# LIN_break.net
KiCad netlist of a schematic drawn in Altium Designer
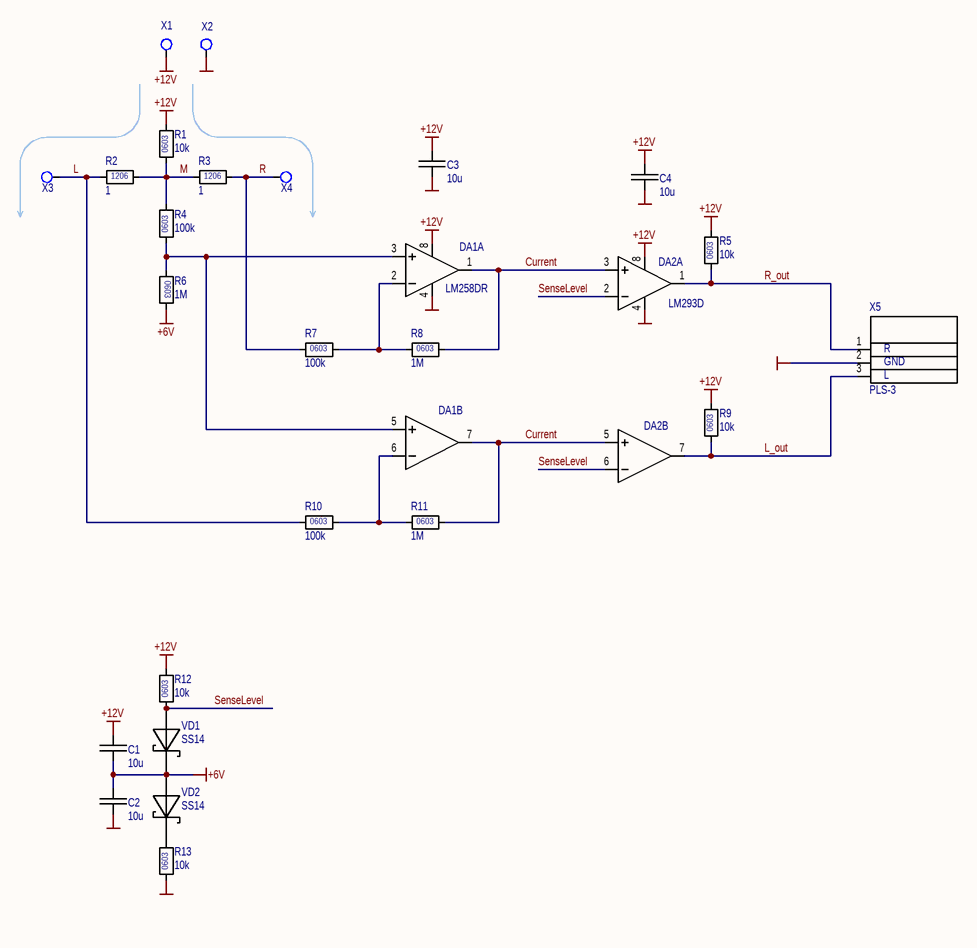
[diagram p0: LIN_break.SchDoc]

(export (version "E")
  (design (tool "Eeschema 10.0.6"))
  (components
    (comp (ref "C1")
      (value "10u")
      (footprint "C0603")
      (description "General  ceramic capacitor")
      (fields
        (field (name "PART NUMBER") "GRM188R61E106MA73#")
        (field (name "ALT PART") "C1608X5R106MFT(Darfon) C1608X5R1E106M080AC(TDK)")
      )
      (libsource (lib "altium") (part "Capacitor"))
    )
    (comp (ref "C2")
      (value "10u")
      (footprint "C0603")
      (description "General  ceramic capacitor")
      (fields
        (field (name "PART NUMBER") "GRM188R61E106MA73#")
        (field (name "ALT PART") "C1608X5R106MFT(Darfon) C1608X5R1E106M080AC(TDK)")
      )
      (libsource (lib "altium") (part "Capacitor"))
    )
    (comp (ref "C3")
      (value "10u")
      (footprint "C0603")
      (description "General  ceramic capacitor")
      (fields
        (field (name "PART NUMBER") "GRM188R61E106MA73#")
        (field (name "ALT PART") "C1608X5R106MFT(Darfon) C1608X5R1E106M080AC(TDK)")
      )
      (libsource (lib "altium") (part "Capacitor"))
    )
    (comp (ref "C4")
      (value "10u")
      (footprint "C0603")
      (description "General  ceramic capacitor")
      (fields
        (field (name "PART NUMBER") "GRM188R61E106MA73#")
        (field (name "ALT PART") "C1608X5R106MFT(Darfon) C1608X5R1E106M080AC(TDK)")
      )
      (libsource (lib "altium") (part "Capacitor"))
    )
    (comp (ref "DA1")
      (value "LM258")
      (footprint "TI-SOIC8 D")
      (description "Op Amp")
      (fields (field (name "PART NUMBER") "LM258DR"))
      (libsource (lib "altium") (part "LMx58_LM2904"))
    )
    (comp (ref "DA2")
      (value "Comparator")
      (footprint "TI-SOIC8 D")
      (description "Dual Comparator OK")
      (fields (field (name "PART NUMBER") "LM293D"))
      (libsource (lib "altium") (part "LMx93_LM2903"))
    )
    (comp (ref "R1")
      (value "10k")
      (footprint "R0603")
      (description "Thick Film Chip Resistor - CR Series")
      (fields (field (name "PART NUMBER") "CR-03FL7---10k") (field (name "ALT PART") "RTT031002FTH (Ralec)"))
      (libsource (lib "altium") (part "Resistor - 0603"))
    )
    (comp (ref "R2")
      (value "1")
      (footprint "R1206")
      (description "1/4W 200V")
      (fields (field (name "PART NUMBER") "CR-06FL5---1R0") (field (name "POWER") "1/4W"))
      (libsource (lib "altium") (part "Resistor - 1206"))
    )
    (comp (ref "R3")
      (value "1")
      (footprint "R1206")
      (description "1/4W 200V")
      (fields (field (name "PART NUMBER") "CR-06FL5---1R0") (field (name "POWER") "1/4W"))
      (libsource (lib "altium") (part "Resistor - 1206"))
    )
    (comp (ref "R4")
      (value "100k")
      (footprint "R0603")
      (description "Thick Film Chip Resistor - CR Series")
      (fields (field (name "PART NUMBER") "CR-03FL7----1M") (field (name "ALT PART") "RTT031004FTH (Ralec)"))
      (libsource (lib "altium") (part "Resistor - 0603"))
    )
    (comp (ref "R5")
      (value "10k")
      (footprint "R0603")
      (description "Thick Film Chip Resistor - CR Series")
      (fields (field (name "PART NUMBER") "CR-03FL7---10k") (field (name "ALT PART") "RTT031002FTH (Ralec)"))
      (libsource (lib "altium") (part "Resistor - 0603"))
    )
    (comp (ref "R6")
      (value "1M")
      (footprint "R0603")
      (description "Thick Film Chip Resistor - CR Series")
      (fields (field (name "PART NUMBER") "CR-03FL7----1M") (field (name "ALT PART") "RTT031004FTH (Ralec)"))
      (libsource (lib "altium") (part "Resistor - 0603"))
    )
    (comp (ref "R7")
      (value "100k")
      (footprint "R0603")
      (description "Thick Film Chip Resistor - CR Series")
      (fields (field (name "PART NUMBER") "CR-03FL7----1M") (field (name "ALT PART") "RTT031004FTH (Ralec)"))
      (libsource (lib "altium") (part "Resistor - 0603"))
    )
    (comp (ref "R8")
      (value "1M")
      (footprint "R0603")
      (description "Thick Film Chip Resistor - CR Series")
      (fields (field (name "PART NUMBER") "CR-03FL7----1M") (field (name "ALT PART") "RTT031004FTH (Ralec)"))
      (libsource (lib "altium") (part "Resistor - 0603"))
    )
    (comp (ref "R9")
      (value "10k")
      (footprint "R0603")
      (description "Thick Film Chip Resistor - CR Series")
      (fields (field (name "PART NUMBER") "CR-03FL7---10k") (field (name "ALT PART") "RTT031002FTH (Ralec)"))
      (libsource (lib "altium") (part "Resistor - 0603"))
    )
    (comp (ref "R10")
      (value "100k")
      (footprint "R0603")
      (description "Thick Film Chip Resistor - CR Series")
      (fields (field (name "PART NUMBER") "CR-03FL7----1M") (field (name "ALT PART") "RTT031004FTH (Ralec)"))
      (libsource (lib "altium") (part "Resistor - 0603"))
    )
    (comp (ref "R11")
      (value "1M")
      (footprint "R0603")
      (description "Thick Film Chip Resistor - CR Series")
      (fields (field (name "PART NUMBER") "CR-03FL7----1M") (field (name "ALT PART") "RTT031004FTH (Ralec)"))
      (libsource (lib "altium") (part "Resistor - 0603"))
    )
    (comp (ref "R12")
      (value "10k")
      (footprint "R0603")
      (description "Thick Film Chip Resistor - CR Series")
      (fields (field (name "PART NUMBER") "CR-03FL7---10k") (field (name "ALT PART") "RTT031002FTH (Ralec)"))
      (libsource (lib "altium") (part "Resistor - 0603"))
    )
    (comp (ref "R13")
      (value "10k")
      (footprint "R0603")
      (description "Thick Film Chip Resistor - CR Series")
      (fields (field (name "PART NUMBER") "CR-03FL7---10k") (field (name "ALT PART") "RTT031002FTH (Ralec)"))
      (libsource (lib "altium") (part "Resistor - 0603"))
    )
    (comp (ref "VD1")
      (value "SS14")
      (footprint "DO-214AC(SMA)")
      (description "40V 1A Schottky diode")
      (libsource (lib "altium") (part "Schottky diode"))
    )
    (comp (ref "VD2")
      (value "SS14")
      (footprint "DO-214AC(SMA)")
      (description "40V 1A Schottky diode")
      (libsource (lib "altium") (part "Schottky diode"))
    )
    (comp (ref "X1")
      (value "1-pin_round NB")
      (footprint "Hole-2.4-5")
      (description "M2 x .4 Screw with Lock Washer")
      (libsource (lib "altium") (part "1-pin_round NB"))
    )
    (comp (ref "X2")
      (value "1-pin_round NB")
      (footprint "Hole-2.4-5")
      (description "M2 x .4 Screw with Lock Washer")
      (libsource (lib "altium") (part "1-pin_round NB"))
    )
    (comp (ref "X3")
      (value "1-pin_round NB")
      (footprint "Hole-2.4-5")
      (description "M2 x .4 Screw with Lock Washer")
      (libsource (lib "altium") (part "1-pin_round NB"))
    )
    (comp (ref "X4")
      (value "1-pin_round NB")
      (footprint "Hole-2.4-5")
      (description "M2 x .4 Screw with Lock Washer")
      (libsource (lib "altium") (part "1-pin_round NB"))
    )
    (comp (ref "X5") (value "PLS-3") (footprint "PLS-3") (libsource (lib "altium") (part "Connector-3")))
  )
  (nets
    (net (code "1") (name "+6V") (class "Default")
      (node (ref "C1") (pin "2") (pinfunction "2_2") (pintype "passive"))
      (node (ref "C2") (pin "1") (pinfunction "1_1") (pintype "passive"))
      (node (ref "R6") (pin "2") (pinfunction "2_2") (pintype "passive"))
      (node (ref "VD1") (pin "1") (pinfunction "C_1") (pintype "passive"))
      (node (ref "VD2") (pin "2") (pinfunction "A_2") (pintype "passive"))
    )
    (net (code "2") (name "+12V") (class "Default")
      (node (ref "C1") (pin "1") (pinfunction "1_1") (pintype "passive"))
      (node (ref "C3") (pin "1") (pinfunction "1_1") (pintype "passive"))
      (node (ref "C4") (pin "1") (pinfunction "1_1") (pintype "passive"))
      (node (ref "DA1") (pin "8") (pinfunction "VCC_8") (pintype "passive"))
      (node (ref "DA2") (pin "8") (pinfunction "VCC_8") (pintype "passive"))
      (node (ref "R1") (pin "2") (pinfunction "2_2") (pintype "passive"))
      (node (ref "R12") (pin "2") (pinfunction "2_2") (pintype "passive"))
      (node (ref "R5") (pin "2") (pinfunction "2_2") (pintype "passive"))
      (node (ref "R9") (pin "2") (pinfunction "2_2") (pintype "passive"))
      (node (ref "X1") (pin "1") (pintype "passive"))
    )
    (net (code "3") (name "/Current") (class "Default")
      (node (ref "DA1") (pin "1") (pinfunction "1OUT_1") (pintype "passive"))
      (node (ref "DA1") (pin "7") (pinfunction "2OUT_7") (pintype "passive"))
      (node (ref "DA2") (pin "3") (pinfunction "1IN+_3") (pintype "passive"))
      (node (ref "DA2") (pin "5") (pinfunction "2IN+_5") (pintype "passive"))
      (node (ref "R11") (pin "2") (pinfunction "2_2") (pintype "passive"))
      (node (ref "R8") (pin "2") (pinfunction "2_2") (pintype "passive"))
    )
    (net (code "4") (name "/L") (class "Default")
      (node (ref "R10") (pin "1") (pinfunction "1_1") (pintype "passive"))
      (node (ref "R2") (pin "1") (pinfunction "1_1") (pintype "passive"))
      (node (ref "X3") (pin "1") (pintype "passive"))
    )
    (net (code "5") (name "/L_out") (class "Default")
      (node (ref "DA2") (pin "7") (pinfunction "2OUT_7") (pintype "passive"))
      (node (ref "R9") (pin "1") (pinfunction "1_1") (pintype "passive"))
      (node (ref "X5") (pin "3") (pintype "passive"))
    )
    (net (code "6") (name "/M") (class "Default")
      (node (ref "R1") (pin "1") (pinfunction "1_1") (pintype "passive"))
      (node (ref "R2") (pin "2") (pinfunction "2_2") (pintype "passive"))
      (node (ref "R3") (pin "1") (pinfunction "1_1") (pintype "passive"))
      (node (ref "R4") (pin "2") (pinfunction "2_2") (pintype "passive"))
    )
    (net (code "7") (name "/R") (class "Default")
      (node (ref "R3") (pin "2") (pinfunction "2_2") (pintype "passive"))
      (node (ref "R7") (pin "1") (pinfunction "1_1") (pintype "passive"))
      (node (ref "X4") (pin "1") (pintype "passive"))
    )
    (net (code "8") (name "/R_out") (class "Default")
      (node (ref "DA2") (pin "1") (pinfunction "1OUT_1") (pintype "passive"))
      (node (ref "R5") (pin "1") (pinfunction "1_1") (pintype "passive"))
      (node (ref "X5") (pin "1") (pintype "passive"))
    )
    (net (code "9") (name "/SenseLevel") (class "Default")
      (node (ref "DA2") (pin "2") (pinfunction "1IN-_2") (pintype "passive"))
      (node (ref "DA2") (pin "6") (pinfunction "2IN-_6") (pintype "passive"))
      (node (ref "R12") (pin "1") (pinfunction "1_1") (pintype "passive"))
      (node (ref "VD1") (pin "2") (pinfunction "A_2") (pintype "passive"))
    )
    (net (code "10") (name "GND") (class "Default")
      (node (ref "C2") (pin "2") (pinfunction "2_2") (pintype "passive"))
      (node (ref "C3") (pin "2") (pinfunction "2_2") (pintype "passive"))
      (node (ref "C4") (pin "2") (pinfunction "2_2") (pintype "passive"))
      (node (ref "DA1") (pin "4") (pinfunction "GND_4") (pintype "passive"))
      (node (ref "DA2") (pin "4") (pinfunction "GND_4") (pintype "passive"))
      (node (ref "R13") (pin "1") (pinfunction "1_1") (pintype "passive"))
      (node (ref "X2") (pin "1") (pintype "passive"))
      (node (ref "X5") (pin "2") (pintype "passive"))
    )
    (net (code "11") (name "Net-(DA1A-1IN+)") (class "Default")
      (node (ref "DA1") (pin "3") (pinfunction "1IN+_3") (pintype "passive"))
      (node (ref "DA1") (pin "5") (pinfunction "2IN+_5") (pintype "passive"))
      (node (ref "R4") (pin "1") (pinfunction "1_1") (pintype "passive"))
      (node (ref "R6") (pin "1") (pinfunction "1_1") (pintype "passive"))
    )
    (net (code "12") (name "Net-(DA1A-1IN-)") (class "Default")
      (node (ref "DA1") (pin "2") (pinfunction "1IN-_2") (pintype "passive"))
      (node (ref "R7") (pin "2") (pinfunction "2_2") (pintype "passive"))
      (node (ref "R8") (pin "1") (pinfunction "1_1") (pintype "passive"))
    )
    (net (code "13") (name "Net-(DA1B-2IN-)") (class "Default")
      (node (ref "DA1") (pin "6") (pinfunction "2IN-_6") (pintype "passive"))
      (node (ref "R10") (pin "2") (pinfunction "2_2") (pintype "passive"))
      (node (ref "R11") (pin "1") (pinfunction "1_1") (pintype "passive"))
    )
    (net (code "14") (name "Net-(VD2-C)") (class "Default")
      (node (ref "R13") (pin "2") (pinfunction "2_2") (pintype "passive"))
      (node (ref "VD2") (pin "1") (pinfunction "C_1") (pintype "passive"))
    )
  )
)
